# untitled.net
KiCad netlist of a schematic drawn in EAGLE
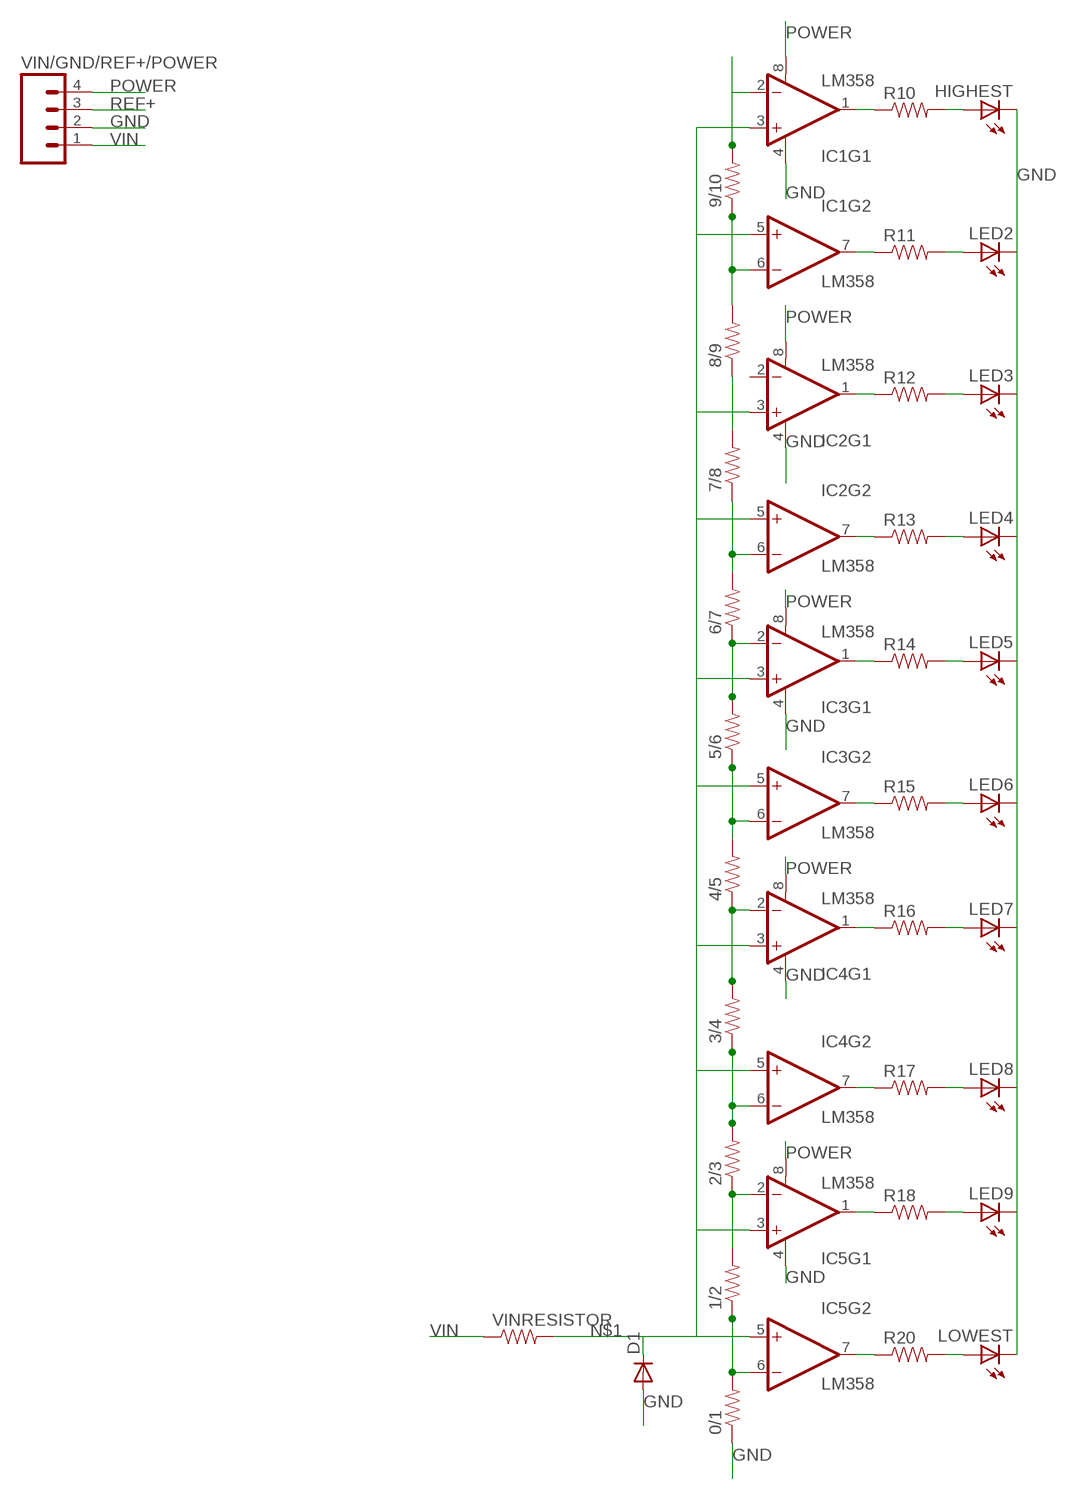
[diagram p0: schematic, sheet 1]

(export (version "E")
  (design (tool "Eeschema 10.0.6"))
  (components
    (comp (ref "0/1")
      (value "RESISTORPTH-1/4W")
      (footprint "eagle-import:AXIAL-0.4")
      (libsource (lib "eagle-import") (part "RESISTORPTH-1/4W"))
    )
    (comp (ref "1/2")
      (value "RESISTORPTH-1/4W")
      (footprint "eagle-import:AXIAL-0.4")
      (libsource (lib "eagle-import") (part "RESISTORPTH-1/4W"))
    )
    (comp (ref "2/3")
      (value "RESISTORPTH-1/4W")
      (footprint "eagle-import:AXIAL-0.4")
      (libsource (lib "eagle-import") (part "RESISTORPTH-1/4W"))
    )
    (comp (ref "3/4")
      (value "RESISTORPTH-1/4W")
      (footprint "eagle-import:AXIAL-0.4")
      (libsource (lib "eagle-import") (part "RESISTORPTH-1/4W"))
    )
    (comp (ref "4/5")
      (value "RESISTORPTH-1/4W")
      (footprint "eagle-import:AXIAL-0.4")
      (libsource (lib "eagle-import") (part "RESISTORPTH-1/4W"))
    )
    (comp (ref "5/6")
      (value "RESISTORPTH-1/4W")
      (footprint "eagle-import:AXIAL-0.4")
      (libsource (lib "eagle-import") (part "RESISTORPTH-1/4W"))
    )
    (comp (ref "6/7")
      (value "RESISTORPTH-1/4W")
      (footprint "eagle-import:AXIAL-0.4")
      (libsource (lib "eagle-import") (part "RESISTORPTH-1/4W"))
    )
    (comp (ref "7/8")
      (value "RESISTORPTH-1/4W")
      (footprint "eagle-import:AXIAL-0.4")
      (libsource (lib "eagle-import") (part "RESISTORPTH-1/4W"))
    )
    (comp (ref "8/9")
      (value "RESISTORPTH-1/4W")
      (footprint "eagle-import:AXIAL-0.4")
      (libsource (lib "eagle-import") (part "RESISTORPTH-1/4W"))
    )
    (comp (ref "9/10")
      (value "RESISTORPTH-1/4W")
      (footprint "eagle-import:AXIAL-0.4")
      (libsource (lib "eagle-import") (part "RESISTORPTH-1/4W"))
    )
    (comp (ref "D1")
      (value "DIODE1N4148")
      (footprint "eagle-import:DIODE-1N4148")
      (libsource (lib "eagle-import") (part "DIODE1N4148"))
    )
    (comp (ref "HIGHEST")
      (value "LED5MM")
      (footprint "eagle-import:LED5MM")
      (libsource (lib "eagle-import") (part "LED5MM"))
    )
    (comp (ref "IC1")
      (value "LM358")
      (footprint "eagle-import:DIP08")
      (libsource (lib "eagle-import") (part "LM358"))
    )
    (comp (ref "IC2")
      (value "LM358")
      (footprint "eagle-import:DIP08")
      (libsource (lib "eagle-import") (part "LM358"))
    )
    (comp (ref "IC3")
      (value "LM358")
      (footprint "eagle-import:DIP08")
      (libsource (lib "eagle-import") (part "LM358"))
    )
    (comp (ref "IC4")
      (value "LM358")
      (footprint "eagle-import:DIP08")
      (libsource (lib "eagle-import") (part "LM358"))
    )
    (comp (ref "IC5")
      (value "LM358")
      (footprint "eagle-import:DIP08")
      (libsource (lib "eagle-import") (part "LM358"))
    )
    (comp (ref "LED2")
      (value "LED5MM")
      (footprint "eagle-import:LED5MM")
      (libsource (lib "eagle-import") (part "LED5MM"))
    )
    (comp (ref "LED3")
      (value "LED5MM")
      (footprint "eagle-import:LED5MM")
      (libsource (lib "eagle-import") (part "LED5MM"))
    )
    (comp (ref "LED4")
      (value "LED5MM")
      (footprint "eagle-import:LED5MM")
      (libsource (lib "eagle-import") (part "LED5MM"))
    )
    (comp (ref "LED5")
      (value "LED5MM")
      (footprint "eagle-import:LED5MM")
      (libsource (lib "eagle-import") (part "LED5MM"))
    )
    (comp (ref "LED6")
      (value "LED5MM")
      (footprint "eagle-import:LED5MM")
      (libsource (lib "eagle-import") (part "LED5MM"))
    )
    (comp (ref "LED7")
      (value "LED5MM")
      (footprint "eagle-import:LED5MM")
      (libsource (lib "eagle-import") (part "LED5MM"))
    )
    (comp (ref "LED8")
      (value "LED5MM")
      (footprint "eagle-import:LED5MM")
      (libsource (lib "eagle-import") (part "LED5MM"))
    )
    (comp (ref "LED9")
      (value "LED5MM")
      (footprint "eagle-import:LED5MM")
      (libsource (lib "eagle-import") (part "LED5MM"))
    )
    (comp (ref "LOWEST")
      (value "LED5MM")
      (footprint "eagle-import:LED5MM")
      (libsource (lib "eagle-import") (part "LED5MM"))
    )
    (comp (ref "R10")
      (value "RESISTORPTH-1/4W")
      (footprint "eagle-import:AXIAL-0.4")
      (libsource (lib "eagle-import") (part "RESISTORPTH-1/4W"))
    )
    (comp (ref "R11")
      (value "RESISTORPTH-1/4W")
      (footprint "eagle-import:AXIAL-0.4")
      (libsource (lib "eagle-import") (part "RESISTORPTH-1/4W"))
    )
    (comp (ref "R12")
      (value "RESISTORPTH-1/4W")
      (footprint "eagle-import:AXIAL-0.4")
      (libsource (lib "eagle-import") (part "RESISTORPTH-1/4W"))
    )
    (comp (ref "R13")
      (value "RESISTORPTH-1/4W")
      (footprint "eagle-import:AXIAL-0.4")
      (libsource (lib "eagle-import") (part "RESISTORPTH-1/4W"))
    )
    (comp (ref "R14")
      (value "RESISTORPTH-1/4W")
      (footprint "eagle-import:AXIAL-0.4")
      (libsource (lib "eagle-import") (part "RESISTORPTH-1/4W"))
    )
    (comp (ref "R15")
      (value "RESISTORPTH-1/4W")
      (footprint "eagle-import:AXIAL-0.4")
      (libsource (lib "eagle-import") (part "RESISTORPTH-1/4W"))
    )
    (comp (ref "R16")
      (value "RESISTORPTH-1/4W")
      (footprint "eagle-import:AXIAL-0.4")
      (libsource (lib "eagle-import") (part "RESISTORPTH-1/4W"))
    )
    (comp (ref "R17")
      (value "RESISTORPTH-1/4W")
      (footprint "eagle-import:AXIAL-0.4")
      (libsource (lib "eagle-import") (part "RESISTORPTH-1/4W"))
    )
    (comp (ref "R18")
      (value "RESISTORPTH-1/4W")
      (footprint "eagle-import:AXIAL-0.4")
      (libsource (lib "eagle-import") (part "RESISTORPTH-1/4W"))
    )
    (comp (ref "R20")
      (value "RESISTORPTH-1/4W")
      (footprint "eagle-import:AXIAL-0.4")
      (libsource (lib "eagle-import") (part "RESISTORPTH-1/4W"))
    )
    (comp (ref "VIN/GND/REF+/POWER")
      (value "M04PTH")
      (footprint "eagle-import:1X04")
      (libsource (lib "eagle-import") (part "M04PTH"))
    )
    (comp (ref "VINRESISTOR")
      (value "RESISTORPTH-1/4W")
      (footprint "eagle-import:AXIAL-0.4")
      (libsource (lib "eagle-import") (part "RESISTORPTH-1/4W"))
    )
  )
  (nets
    (net (code "1") (name "/GND") (class "Default")
      (node (ref "0/1") (pin "P$1") (pinfunction "1_P$1") (pintype "passive"))
      (node (ref "D1") (pin "A") (pinfunction "A_A") (pintype "passive"))
      (node (ref "HIGHEST") (pin "K") (pinfunction "C_K") (pintype "passive"))
      (node (ref "IC1") (pin "4") (pinfunction "V-_4") (pintype "power_in"))
      (node (ref "IC2") (pin "4") (pinfunction "V-_4") (pintype "power_in"))
      (node (ref "IC3") (pin "4") (pinfunction "V-_4") (pintype "power_in"))
      (node (ref "IC4") (pin "4") (pinfunction "V-_4") (pintype "power_in"))
      (node (ref "IC5") (pin "4") (pinfunction "V-_4") (pintype "power_in"))
      (node (ref "LED2") (pin "K") (pinfunction "C_K") (pintype "passive"))
      (node (ref "LED3") (pin "K") (pinfunction "C_K") (pintype "passive"))
      (node (ref "LED4") (pin "K") (pinfunction "C_K") (pintype "passive"))
      (node (ref "LED5") (pin "K") (pinfunction "C_K") (pintype "passive"))
      (node (ref "LED6") (pin "K") (pinfunction "C_K") (pintype "passive"))
      (node (ref "LED7") (pin "K") (pinfunction "C_K") (pintype "passive"))
      (node (ref "LED8") (pin "K") (pinfunction "C_K") (pintype "passive"))
      (node (ref "LED9") (pin "K") (pinfunction "C_K") (pintype "passive"))
      (node (ref "LOWEST") (pin "K") (pinfunction "C_K") (pintype "passive"))
      (node (ref "VIN/GND/REF+/POWER") (pin "2") (pinfunction "2_2") (pintype "passive"))
    )
    (net (code "2") (name "/N$1") (class "Default")
      (node (ref "D1") (pin "C") (pinfunction "C_C") (pintype "passive"))
      (node (ref "IC1") (pin "3") (pinfunction "+IN_3") (pintype "input"))
      (node (ref "IC1") (pin "5") (pinfunction "+IN_5") (pintype "input"))
      (node (ref "IC2") (pin "3") (pinfunction "+IN_3") (pintype "input"))
      (node (ref "IC2") (pin "5") (pinfunction "+IN_5") (pintype "input"))
      (node (ref "IC3") (pin "3") (pinfunction "+IN_3") (pintype "input"))
      (node (ref "IC3") (pin "5") (pinfunction "+IN_5") (pintype "input"))
      (node (ref "IC4") (pin "3") (pinfunction "+IN_3") (pintype "input"))
      (node (ref "IC4") (pin "5") (pinfunction "+IN_5") (pintype "input"))
      (node (ref "IC5") (pin "3") (pinfunction "+IN_3") (pintype "input"))
      (node (ref "IC5") (pin "5") (pinfunction "+IN_5") (pintype "input"))
      (node (ref "VINRESISTOR") (pin "P$2") (pinfunction "2_P$2") (pintype "passive"))
    )
    (net (code "3") (name "/POWER") (class "Default")
      (node (ref "IC1") (pin "8") (pinfunction "V+_8") (pintype "power_in"))
      (node (ref "IC2") (pin "8") (pinfunction "V+_8") (pintype "power_in"))
      (node (ref "IC3") (pin "8") (pinfunction "V+_8") (pintype "power_in"))
      (node (ref "IC4") (pin "8") (pinfunction "V+_8") (pintype "power_in"))
      (node (ref "IC5") (pin "8") (pinfunction "V+_8") (pintype "power_in"))
      (node (ref "VIN/GND/REF+/POWER") (pin "4") (pinfunction "4_4") (pintype "passive"))
    )
    (net (code "4") (name "/REF+") (class "Default")
      (node (ref "9/10") (pin "P$2") (pinfunction "2_P$2") (pintype "passive"))
      (node (ref "IC1") (pin "2") (pinfunction "-IN_2") (pintype "input"))
      (node (ref "VIN/GND/REF+/POWER") (pin "3") (pinfunction "3_3") (pintype "passive"))
    )
    (net (code "5") (name "/VIN") (class "Default")
      (node (ref "VIN/GND/REF+/POWER") (pin "1") (pinfunction "1_1") (pintype "passive"))
      (node (ref "VINRESISTOR") (pin "P$1") (pinfunction "1_P$1") (pintype "passive"))
    )
    (net (code "6") (name "Net-(0/1-2)") (class "Default")
      (node (ref "0/1") (pin "P$2") (pinfunction "2_P$2") (pintype "passive"))
      (node (ref "1/2") (pin "P$1") (pinfunction "1_P$1") (pintype "passive"))
      (node (ref "IC5") (pin "6") (pinfunction "-IN_6") (pintype "input"))
    )
    (net (code "7") (name "Net-(1/2-2)") (class "Default")
      (node (ref "1/2") (pin "P$2") (pinfunction "2_P$2") (pintype "passive"))
      (node (ref "2/3") (pin "P$1") (pinfunction "1_P$1") (pintype "passive"))
      (node (ref "IC5") (pin "2") (pinfunction "-IN_2") (pintype "input"))
    )
    (net (code "8") (name "Net-(2/3-2)") (class "Default")
      (node (ref "2/3") (pin "P$2") (pinfunction "2_P$2") (pintype "passive"))
      (node (ref "3/4") (pin "P$1") (pinfunction "1_P$1") (pintype "passive"))
      (node (ref "IC4") (pin "6") (pinfunction "-IN_6") (pintype "input"))
    )
    (net (code "9") (name "Net-(3/4-2)") (class "Default")
      (node (ref "3/4") (pin "P$2") (pinfunction "2_P$2") (pintype "passive"))
      (node (ref "4/5") (pin "P$1") (pinfunction "1_P$1") (pintype "passive"))
      (node (ref "IC4") (pin "2") (pinfunction "-IN_2") (pintype "input"))
    )
    (net (code "10") (name "Net-(4/5-2)") (class "Default")
      (node (ref "4/5") (pin "P$2") (pinfunction "2_P$2") (pintype "passive"))
      (node (ref "5/6") (pin "P$1") (pinfunction "1_P$1") (pintype "passive"))
      (node (ref "IC3") (pin "6") (pinfunction "-IN_6") (pintype "input"))
    )
    (net (code "11") (name "Net-(5/6-2)") (class "Default")
      (node (ref "5/6") (pin "P$2") (pinfunction "2_P$2") (pintype "passive"))
      (node (ref "6/7") (pin "P$1") (pinfunction "1_P$1") (pintype "passive"))
      (node (ref "IC3") (pin "2") (pinfunction "-IN_2") (pintype "input"))
    )
    (net (code "12") (name "Net-(6/7-2)") (class "Default")
      (node (ref "6/7") (pin "P$2") (pinfunction "2_P$2") (pintype "passive"))
      (node (ref "7/8") (pin "P$1") (pinfunction "1_P$1") (pintype "passive"))
      (node (ref "IC2") (pin "6") (pinfunction "-IN_6") (pintype "input"))
    )
    (net (code "13") (name "Net-(7/8-2)") (class "Default")
      (node (ref "7/8") (pin "P$2") (pinfunction "2_P$2") (pintype "passive"))
      (node (ref "8/9") (pin "P$1") (pinfunction "1_P$1") (pintype "passive"))
    )
    (net (code "14") (name "Net-(8/9-2)") (class "Default")
      (node (ref "8/9") (pin "P$2") (pinfunction "2_P$2") (pintype "passive"))
      (node (ref "9/10") (pin "P$1") (pinfunction "1_P$1") (pintype "passive"))
      (node (ref "IC1") (pin "6") (pinfunction "-IN_6") (pintype "input"))
    )
    (net (code "15") (name "Net-(IC1A-OUT)") (class "Default")
      (node (ref "IC1") (pin "1") (pinfunction "OUT_1") (pintype "output"))
      (node (ref "R10") (pin "P$1") (pinfunction "1_P$1") (pintype "passive"))
    )
    (net (code "16") (name "Net-(IC1B-OUT)") (class "Default")
      (node (ref "IC1") (pin "7") (pinfunction "OUT_7") (pintype "output"))
      (node (ref "R11") (pin "P$1") (pinfunction "1_P$1") (pintype "passive"))
    )
    (net (code "17") (name "Net-(IC2A-OUT)") (class "Default")
      (node (ref "IC2") (pin "1") (pinfunction "OUT_1") (pintype "output"))
      (node (ref "R12") (pin "P$1") (pinfunction "1_P$1") (pintype "passive"))
    )
    (net (code "18") (name "Net-(IC2B-OUT)") (class "Default")
      (node (ref "IC2") (pin "7") (pinfunction "OUT_7") (pintype "output"))
      (node (ref "R13") (pin "P$1") (pinfunction "1_P$1") (pintype "passive"))
    )
    (net (code "19") (name "Net-(IC3A-OUT)") (class "Default")
      (node (ref "IC3") (pin "1") (pinfunction "OUT_1") (pintype "output"))
      (node (ref "R14") (pin "P$1") (pinfunction "1_P$1") (pintype "passive"))
    )
    (net (code "20") (name "Net-(IC3B-OUT)") (class "Default")
      (node (ref "IC3") (pin "7") (pinfunction "OUT_7") (pintype "output"))
      (node (ref "R15") (pin "P$1") (pinfunction "1_P$1") (pintype "passive"))
    )
    (net (code "21") (name "Net-(IC4A-OUT)") (class "Default")
      (node (ref "IC4") (pin "1") (pinfunction "OUT_1") (pintype "output"))
      (node (ref "R16") (pin "P$1") (pinfunction "1_P$1") (pintype "passive"))
    )
    (net (code "22") (name "Net-(IC4B-OUT)") (class "Default")
      (node (ref "IC4") (pin "7") (pinfunction "OUT_7") (pintype "output"))
      (node (ref "R17") (pin "P$1") (pinfunction "1_P$1") (pintype "passive"))
    )
    (net (code "23") (name "Net-(IC5A-OUT)") (class "Default")
      (node (ref "IC5") (pin "1") (pinfunction "OUT_1") (pintype "output"))
      (node (ref "R18") (pin "P$1") (pinfunction "1_P$1") (pintype "passive"))
    )
    (net (code "24") (name "Net-(IC5B-OUT)") (class "Default")
      (node (ref "IC5") (pin "7") (pinfunction "OUT_7") (pintype "output"))
      (node (ref "R20") (pin "P$1") (pinfunction "1_P$1") (pintype "passive"))
    )
    (net (code "25") (name "Net-(R10-2)") (class "Default")
      (node (ref "HIGHEST") (pin "A") (pinfunction "A_A") (pintype "passive"))
      (node (ref "R10") (pin "P$2") (pinfunction "2_P$2") (pintype "passive"))
    )
    (net (code "26") (name "Net-(R11-2)") (class "Default")
      (node (ref "LED2") (pin "A") (pinfunction "A_A") (pintype "passive"))
      (node (ref "R11") (pin "P$2") (pinfunction "2_P$2") (pintype "passive"))
    )
    (net (code "27") (name "Net-(R12-2)") (class "Default")
      (node (ref "LED3") (pin "A") (pinfunction "A_A") (pintype "passive"))
      (node (ref "R12") (pin "P$2") (pinfunction "2_P$2") (pintype "passive"))
    )
    (net (code "28") (name "Net-(R13-2)") (class "Default")
      (node (ref "LED4") (pin "A") (pinfunction "A_A") (pintype "passive"))
      (node (ref "R13") (pin "P$2") (pinfunction "2_P$2") (pintype "passive"))
    )
    (net (code "29") (name "Net-(R14-2)") (class "Default")
      (node (ref "LED5") (pin "A") (pinfunction "A_A") (pintype "passive"))
      (node (ref "R14") (pin "P$2") (pinfunction "2_P$2") (pintype "passive"))
    )
    (net (code "30") (name "Net-(R15-2)") (class "Default")
      (node (ref "LED6") (pin "A") (pinfunction "A_A") (pintype "passive"))
      (node (ref "R15") (pin "P$2") (pinfunction "2_P$2") (pintype "passive"))
    )
    (net (code "31") (name "Net-(R16-2)") (class "Default")
      (node (ref "LED7") (pin "A") (pinfunction "A_A") (pintype "passive"))
      (node (ref "R16") (pin "P$2") (pinfunction "2_P$2") (pintype "passive"))
    )
    (net (code "32") (name "Net-(R17-2)") (class "Default")
      (node (ref "LED8") (pin "A") (pinfunction "A_A") (pintype "passive"))
      (node (ref "R17") (pin "P$2") (pinfunction "2_P$2") (pintype "passive"))
    )
    (net (code "33") (name "Net-(R18-2)") (class "Default")
      (node (ref "LED9") (pin "A") (pinfunction "A_A") (pintype "passive"))
      (node (ref "R18") (pin "P$2") (pinfunction "2_P$2") (pintype "passive"))
    )
    (net (code "34") (name "Net-(R20-2)") (class "Default")
      (node (ref "LOWEST") (pin "A") (pinfunction "A_A") (pintype "passive"))
      (node (ref "R20") (pin "P$2") (pinfunction "2_P$2") (pintype "passive"))
    )
    (net (code "35") (name "unconnected-(IC2A--IN-Pad2)") (class "Default")
      (node (ref "IC2") (pin "2") (pinfunction "-IN_2") (pintype "input"))
    )
  )
)
